# Synchronous_Buck_Solar_Charge_Controller.net
KiCad netlist of a schematic drawn in Altium Designer
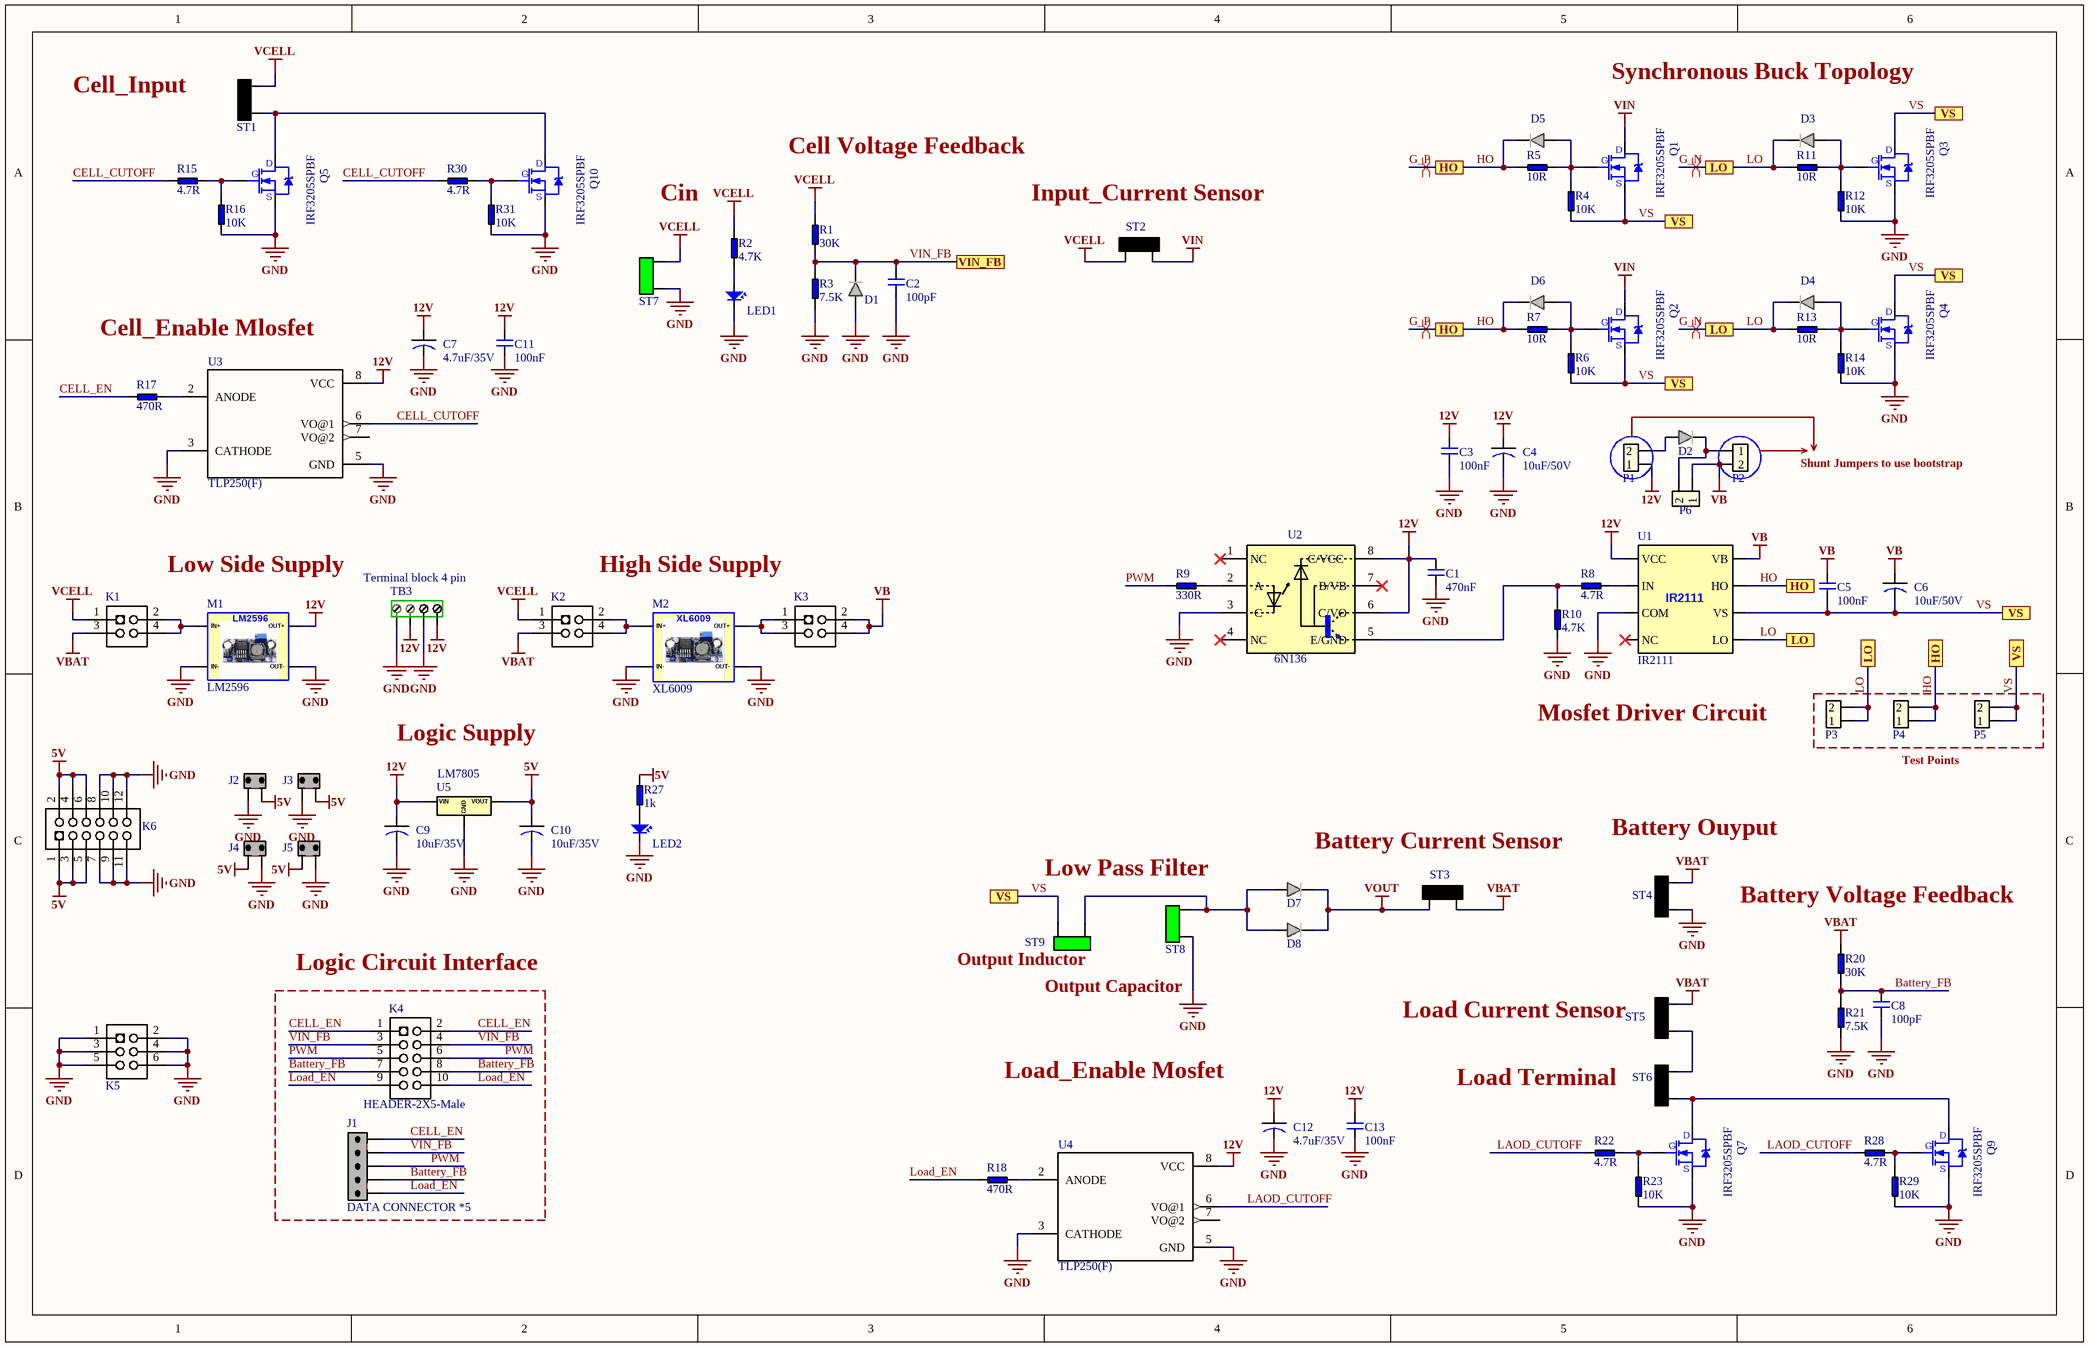
[diagram p0: Synchronous Buck Solar Charge Controller Board.SchDoc]

(export (version "E")
  (design (tool "Eeschema 10.0.6"))
  (components
    (comp (ref "C1")
      (value "470nF")
      (footprint "CCAP 0.1 N Y")
      (libsource (lib "Altium_Abbas") (part "Ceramic_CAP_470nF"))
    )
    (comp (ref "C2")
      (value "100pF")
      (footprint "CCAP 0.1 N Y")
      (libsource (lib "Altium_Abbas") (part "Ceramic_CAP_100pF"))
    )
    (comp (ref "C3")
      (value "100nF")
      (footprint "CCAP 0.1 N Y")
      (libsource (lib "Altium_Abbas") (part "Ceramic_CAP_100nF"))
    )
    (comp (ref "C4")
      (value "10uF/50V")
      (footprint "ECAP 5X11X2MM")
      (description "10uF ±20% 50V 5x11 1000Hrs @ 105℃ Radial,5x11mm Aluminum Electrolytic Capacitors - Leaded RoHS")
      (libsource (lib "Altium_Abbas") (part "ECAP-10uF-50V"))
    )
    (comp (ref "C5")
      (value "100nF")
      (footprint "CCAP 0.1 N Y")
      (libsource (lib "Altium_Abbas") (part "Ceramic_CAP_100nF"))
    )
    (comp (ref "C6")
      (value "10uF/50V")
      (footprint "ECAP 5X11X2MM")
      (description "10uF ±20% 50V 5x11 1000Hrs @ 105℃ Radial,5x11mm Aluminum Electrolytic Capacitors - Leaded RoHS")
      (libsource (lib "Altium_Abbas") (part "ECAP-10uF-50V"))
    )
    (comp (ref "C7")
      (value "4.7uF/35V")
      (footprint "ECAP 5X11X2MM")
      (description "4.7uF ±20% 35V 5x11 7000Hrs @ 105℃ Radial,5x11mm Aluminum Electrolytic Capacitors - Leaded RoHS")
      (libsource (lib "Altium_Abbas") (part "ECAP-4.7uF-35V"))
    )
    (comp (ref "C8")
      (value "100pF")
      (footprint "CCAP 0.1 N Y")
      (libsource (lib "Altium_Abbas") (part "Ceramic_CAP_100pF"))
    )
    (comp (ref "C9")
      (value "10uF/35V")
      (footprint "ECAP 5X11X2MM")
      (description "10uF ±20% 35V 5x11 2000Hrs @ 105℃ Radial,5x11mm Aluminum Electrolytic Capacitors - Leaded RoHS")
      (libsource (lib "Altium_Abbas") (part "ECAP-10uF-35V"))
    )
    (comp (ref "C10")
      (value "10uF/35V")
      (footprint "ECAP 5X11X2MM")
      (description "10uF ±20% 35V 5x11 2000Hrs @ 105℃ Radial,5x11mm Aluminum Electrolytic Capacitors - Leaded RoHS")
      (libsource (lib "Altium_Abbas") (part "ECAP-10uF-35V"))
    )
    (comp (ref "C11")
      (value "100nF")
      (footprint "CCAP 0.1 N Y")
      (libsource (lib "Altium_Abbas") (part "Ceramic_CAP_100nF"))
    )
    (comp (ref "C12")
      (value "4.7uF/35V")
      (footprint "ECAP 5X11X2MM")
      (description "4.7uF ±20% 35V 5x11 7000Hrs @ 105℃ Radial,5x11mm Aluminum Electrolytic Capacitors - Leaded RoHS")
      (libsource (lib "Altium_Abbas") (part "ECAP-4.7uF-35V"))
    )
    (comp (ref "C13")
      (value "100nF")
      (footprint "CCAP 0.1 N Y")
      (libsource (lib "Altium_Abbas") (part "Ceramic_CAP_100nF"))
    )
    (comp (ref "D1")
      (value "DIODE")
      (footprint "DIODE-1N400X_0.1")
      (libsource (lib "Altium_Abbas") (part "DIODE"))
    )
    (comp (ref "D2")
      (value "DIODE")
      (footprint "DIODE-1n400X_0.3")
      (libsource (lib "Altium_Abbas") (part "DIODE"))
    )
    (comp (ref "D3")
      (value "DIODE")
      (footprint "DIODE-1n400X_0.3")
      (libsource (lib "Altium_Abbas") (part "DIODE"))
    )
    (comp (ref "D4")
      (value "DIODE")
      (footprint "DIODE-1n400X_0.3")
      (libsource (lib "Altium_Abbas") (part "DIODE"))
    )
    (comp (ref "D5")
      (value "DIODE")
      (footprint "DIODE-1n400X_0.3")
      (libsource (lib "Altium_Abbas") (part "DIODE"))
    )
    (comp (ref "D6")
      (value "DIODE")
      (footprint "DIODE-1n400X_0.3")
      (libsource (lib "Altium_Abbas") (part "DIODE"))
    )
    (comp (ref "D7")
      (value "10A DIODE")
      (footprint "DIODE 10A 0.75")
      (description "10A05-THRU-10A10\r\nVOLTAGE RANGE 50 to 1000 Volts CURRENT 10 Amperes")
      (libsource (lib "Altium_Abbas") (part "DIODE_10A05"))
    )
    (comp (ref "D8")
      (value "10A DIODE")
      (footprint "DIODE 10A 0.75")
      (description "10A05-THRU-10A10\r\nVOLTAGE RANGE 50 to 1000 Volts CURRENT 10 Amperes")
      (libsource (lib "Altium_Abbas") (part "DIODE_10A05"))
    )
    (comp (ref "J1")
      (value "DATA CONNECTOR *5")
      (footprint "MOLEX *5_DATA CONNECTOR")
      (description "Data Cable JST 5-pin")
      (libsource (lib "Altium_Abbas") (part "DATA CONNECTOR *5"))
    )
    (comp (ref "J2")
      (value "DATA CONNECTOR *2")
      (footprint "MOLEX *2_DATA CONNECTOR")
      (description "Data Cable JST 2-pin")
      (libsource (lib "Altium_Abbas") (part "DATA CONNECTOR *2"))
    )
    (comp (ref "J3")
      (value "DATA CONNECTOR *2")
      (footprint "MOLEX *2_DATA CONNECTOR")
      (description "Data Cable JST 2-pin")
      (libsource (lib "Altium_Abbas") (part "DATA CONNECTOR *2"))
    )
    (comp (ref "J4")
      (value "DATA CONNECTOR *2")
      (footprint "MOLEX *2_DATA CONNECTOR")
      (description "Data Cable JST 2-pin")
      (libsource (lib "Altium_Abbas") (part "DATA CONNECTOR *2"))
    )
    (comp (ref "J5")
      (value "DATA CONNECTOR *2")
      (footprint "MOLEX *2_DATA CONNECTOR")
      (description "Data Cable JST 2-pin")
      (libsource (lib "Altium_Abbas") (part "DATA CONNECTOR *2"))
    )
    (comp (ref "K1")
      (value "HEADER-2X2-Male")
      (footprint "HEADER-2X2")
      (libsource (lib "Altium_Abbas") (part "HEADER-2X2-Male"))
    )
    (comp (ref "K2")
      (value "HEADER-2X2-Male")
      (footprint "HEADER-2X2")
      (libsource (lib "Altium_Abbas") (part "HEADER-2X2-Male"))
    )
    (comp (ref "K3")
      (value "HEADER-2X2-Male")
      (footprint "HEADER-2X2")
      (libsource (lib "Altium_Abbas") (part "HEADER-2X2-Male"))
    )
    (comp (ref "K4")
      (value "HEADER-2X5-Male")
      (footprint "HEADER-2X5")
      (libsource (lib "Altium_Abbas") (part "HEADER-2X5-Male"))
    )
    (comp (ref "K5")
      (value "HEADER-2X3-Male")
      (footprint "HEADER-2X3")
      (libsource (lib "Altium_Abbas") (part "HEADER-2X3-Male"))
    )
    (comp (ref "K6")
      (value "HEADER-2X6-Male")
      (footprint "HEADER-2X6")
      (libsource (lib "Altium_Abbas") (part "HEADER-2X6-Male"))
    )
    (comp (ref "LED1")
      (value "LED")
      (footprint "LED 3MM GREEN")
      (libsource (lib "Altium_Abbas") (part "LED"))
    )
    (comp (ref "LED2") (value "LED") (footprint "LED 3MM BLUE") (libsource (lib "Altium_Abbas") (part "LED")))
    (comp (ref "M1")
      (value "LM2596")
      (footprint "LM2956S BUCK CONVETER")
      (description "ADJUSTABLE DC/DC POWER CONVERTER")
      (libsource (lib "Boards_Abbas") (part "DC TO DC CONVERTER LM2596"))
    )
    (comp (ref "M2")
      (value "XL6009")
      (footprint "DC TO DC CONVERTER XL6009")
      (description "ADJUSTABLE DC/DC POWER CONVERTER")
      (libsource (lib "Boards_Abbas") (part "DC TO DC CONVERTER XL6009"))
    )
    (comp (ref "P1")
      (value "Header - 2 - Male")
      (footprint "PINHEADER X2")
      (description "Header, 2-Pin")
      (fields (field (name "PUBLISHER") "Altium Limited"))
      (libsource (lib "Altium_Abbas") (part "Header - 2 - Male"))
    )
    (comp (ref "P2")
      (value "Header - 2 - Male")
      (footprint "PINHEADER X2")
      (description "Header, 2-Pin")
      (fields (field (name "PUBLISHER") "Altium Limited"))
      (libsource (lib "") (part "Header - 2 - Male_1"))
    )
    (comp (ref "P3")
      (value "Header - 2 - Male")
      (footprint "PINHEADER X2")
      (description "Header, 2-Pin")
      (fields (field (name "PUBLISHER") "Altium Limited"))
      (libsource (lib "Altium_Abbas") (part "Header - 2 - Male"))
    )
    (comp (ref "P4")
      (value "Header - 2 - Male")
      (footprint "PINHEADER X2")
      (description "Header, 2-Pin")
      (fields (field (name "PUBLISHER") "Altium Limited"))
      (libsource (lib "Altium_Abbas") (part "Header - 2 - Male"))
    )
    (comp (ref "P5")
      (value "Header - 2 - Male")
      (footprint "PINHEADER X2")
      (description "Header, 2-Pin")
      (fields (field (name "PUBLISHER") "Altium Limited"))
      (libsource (lib "Altium_Abbas") (part "Header - 2 - Male"))
    )
    (comp (ref "P6")
      (value "Header - 2 - Male")
      (footprint "PINHEADER X2")
      (description "Header, 2-Pin")
      (fields (field (name "PUBLISHER") "Altium Limited"))
      (libsource (lib "") (part "Header - 2 - Male_2"))
    )
    (comp (ref "Q1")
      (value "IRF3205SPBF")
      (footprint "Transistor/Heatsink -TO-220")
      (description "N-Channel 55V 110A _Tc_ 200W _Tc_ Surface Mount D2PAK")
      (fields (field (name "MF") "Infineon Technologies"))
      (libsource (lib "Altium_Abbas") (part "IRF3205SPBF"))
    )
    (comp (ref "Q2")
      (value "IRF3205SPBF")
      (footprint "Transistor/Heatsink -TO-220")
      (description "N-Channel 55V 110A _Tc_ 200W _Tc_ Surface Mount D2PAK")
      (fields (field (name "MF") "Infineon Technologies"))
      (libsource (lib "Altium_Abbas") (part "IRF3205SPBF"))
    )
    (comp (ref "Q3")
      (value "IRF3205SPBF")
      (footprint "Transistor/Heatsink -TO-220")
      (description "N-Channel 55V 110A 200W")
      (fields (field (name "MF") "Infineon Technologies"))
      (libsource (lib "Altium_Abbas") (part "IRF3205SPBF"))
    )
    (comp (ref "Q4")
      (value "IRF3205SPBF")
      (footprint "Transistor/Heatsink -TO-220")
      (description "N-Channel 55V 110A 200W")
      (fields (field (name "MF") "Infineon Technologies"))
      (libsource (lib "Altium_Abbas") (part "IRF3205SPBF"))
    )
    (comp (ref "Q5")
      (value "IRF3205SPBF")
      (footprint "Transistor/Heatsink -TO-220")
      (description "N-Channel 55V 110A 200W")
      (fields (field (name "MF") "Infineon Technologies"))
      (libsource (lib "Altium_Abbas") (part "IRF3205SPBF"))
    )
    (comp (ref "Q7")
      (value "IRF3205SPBF")
      (footprint "Transistor/Heatsink -TO-220")
      (description "N-Channel 55V 110A 200W")
      (fields (field (name "MF") "Infineon Technologies"))
      (libsource (lib "Altium_Abbas") (part "IRF3205SPBF"))
    )
    (comp (ref "Q9")
      (value "IRF3205SPBF")
      (footprint "Transistor/Heatsink -TO-220")
      (description "N-Channel 55V 110A 200W")
      (fields (field (name "MF") "Infineon Technologies"))
      (libsource (lib "Altium_Abbas") (part "IRF3205SPBF"))
    )
    (comp (ref "Q10")
      (value "IRF3205SPBF")
      (footprint "Transistor/Heatsink -TO-220")
      (description "N-Channel 55V 110A 200W")
      (fields (field (name "MF") "Infineon Technologies"))
      (libsource (lib "Altium_Abbas") (part "IRF3205SPBF"))
    )
    (comp (ref "R1")
      (value "30K")
      (footprint "RESISTOR _0")
      (libsource (lib "Altium_Abbas") (part "RESISTOR_30K"))
    )
    (comp (ref "R2")
      (value "4.7K")
      (footprint "RESISTOR _1")
      (libsource (lib "Altium_Abbas") (part "RESISTOR_4.7K"))
    )
    (comp (ref "R3")
      (value "7.5K")
      (footprint "RESISTOR _0")
      (libsource (lib "Altium_Abbas") (part "RESISTOR_7.5K"))
    )
    (comp (ref "R4")
      (value "10K")
      (footprint "RESISTOR _1")
      (libsource (lib "Altium_Abbas") (part "RESISTOR_10K"))
    )
    (comp (ref "R5")
      (value "10R")
      (footprint "RESISTOR _1")
      (libsource (lib "Altium_Abbas") (part "RESISTOR_10R"))
    )
    (comp (ref "R6")
      (value "10K")
      (footprint "RESISTOR _1")
      (libsource (lib "Altium_Abbas") (part "RESISTOR_10K"))
    )
    (comp (ref "R7")
      (value "10R")
      (footprint "RESISTOR _1")
      (libsource (lib "Altium_Abbas") (part "RESISTOR_10R"))
    )
    (comp (ref "R8")
      (value "4.7R")
      (footprint "RESISTOR _0")
      (libsource (lib "Altium_Abbas") (part "RESISTOR_4.7R"))
    )
    (comp (ref "R9")
      (value "330R")
      (footprint "RESISTOR _0")
      (libsource (lib "Altium_Abbas") (part "RESISTOR_330R"))
    )
    (comp (ref "R10")
      (value "4.7K")
      (footprint "RESISTOR _0")
      (libsource (lib "Altium_Abbas") (part "RESISTOR_4.7K"))
    )
    (comp (ref "R11")
      (value "10R")
      (footprint "RESISTOR _1")
      (libsource (lib "Altium_Abbas") (part "RESISTOR_10R"))
    )
    (comp (ref "R12")
      (value "10K")
      (footprint "RESISTOR _1")
      (libsource (lib "Altium_Abbas") (part "RESISTOR_10K"))
    )
    (comp (ref "R13")
      (value "10R")
      (footprint "RESISTOR _1")
      (libsource (lib "Altium_Abbas") (part "RESISTOR_10R"))
    )
    (comp (ref "R14")
      (value "10K")
      (footprint "RESISTOR _1")
      (libsource (lib "Altium_Abbas") (part "RESISTOR_10K"))
    )
    (comp (ref "R15")
      (value "4.7R")
      (footprint "RESISTOR _0")
      (libsource (lib "Altium_Abbas") (part "RESISTOR_4.7R"))
    )
    (comp (ref "R16")
      (value "10K")
      (footprint "RESISTOR _0")
      (libsource (lib "Altium_Abbas") (part "RESISTOR_10K"))
    )
    (comp (ref "R17")
      (value "470R")
      (footprint "RESISTOR _0")
      (libsource (lib "Altium_Abbas") (part "RESISTOR_470R"))
    )
    (comp (ref "R18")
      (value "470R")
      (footprint "RESISTOR _0")
      (libsource (lib "Altium_Abbas") (part "RESISTOR_470R"))
    )
    (comp (ref "R20")
      (value "30K")
      (footprint "RESISTOR _1")
      (libsource (lib "Altium_Abbas") (part "RESISTOR_30K"))
    )
    (comp (ref "R21")
      (value "7.5K")
      (footprint "RESISTOR _1")
      (libsource (lib "Altium_Abbas") (part "RESISTOR_7.5K"))
    )
    (comp (ref "R22")
      (value "4.7R")
      (footprint "RESISTOR _0")
      (libsource (lib "Altium_Abbas") (part "RESISTOR_4.7R"))
    )
    (comp (ref "R23")
      (value "10K")
      (footprint "RESISTOR _0")
      (libsource (lib "Altium_Abbas") (part "RESISTOR_10K"))
    )
    (comp (ref "R27")
      (value "1k")
      (footprint "RESISTOR _0")
      (libsource (lib "Altium_Abbas") (part "RESISTOR_1K"))
    )
    (comp (ref "R28")
      (value "4.7R")
      (footprint "RESISTOR _0")
      (libsource (lib "Altium_Abbas") (part "RESISTOR_4.7R"))
    )
    (comp (ref "R29")
      (value "10K")
      (footprint "RESISTOR _0")
      (libsource (lib "Altium_Abbas") (part "RESISTOR_10K"))
    )
    (comp (ref "R30")
      (value "4.7R")
      (footprint "RESISTOR _0")
      (libsource (lib "Altium_Abbas") (part "RESISTOR_4.7R"))
    )
    (comp (ref "R31")
      (value "10K")
      (footprint "RESISTOR _0")
      (libsource (lib "Altium_Abbas") (part "RESISTOR_10K"))
    )
    (comp (ref "ST1")
      (value "SCREW TERMINAL")
      (footprint "SCREW TERMINAL")
      (description "Barrier Terminal Block 2 Pin with cover 300V/25A")
      (libsource (lib "Altium_Abbas") (part "SCREW TERMINAL"))
    )
    (comp (ref "ST2")
      (value "SCREW TERMINAL")
      (footprint "SCREW TERMINAL")
      (description "Barrier Terminal Block 2 Pin with cover 300V/25A")
      (libsource (lib "") (part "SCREW TERMINAL_2"))
    )
    (comp (ref "ST3")
      (value "SCREW TERMINAL")
      (footprint "SCREW TERMINAL")
      (description "Barrier Terminal Block 2 Pin with cover 300V/25A")
      (libsource (lib "") (part "SCREW TERMINAL_2"))
    )
    (comp (ref "ST4")
      (value "SCREW TERMINAL")
      (footprint "SCREW TERMINAL")
      (description "Barrier Terminal Block 2 Pin with cover 300V/25A")
      (libsource (lib "") (part "SCREW TERMINAL_1"))
    )
    (comp (ref "ST5")
      (value "SCREW TERMINAL")
      (footprint "SCREW TERMINAL")
      (description "Barrier Terminal Block 2 Pin with cover 300V/25A")
      (libsource (lib "") (part "SCREW TERMINAL_1"))
    )
    (comp (ref "ST6")
      (value "SCREW TERMINAL")
      (footprint "SCREW TERMINAL")
      (description "Barrier Terminal Block 2 Pin with cover 300V/25A")
      (libsource (lib "") (part "SCREW TERMINAL_1"))
    )
    (comp (ref "ST7")
      (value "2 Pole Power Terminal")
      (footprint "Screw Terminal Green")
      (description "KF762 Power Terminal Pitch 7.62mm Screw Block Connector 300V 20A 3Pin")
      (libsource (lib "Altium_Abbas") (part "Screw Terminal Green"))
    )
    (comp (ref "ST8")
      (value "2 Pole Power Terminal")
      (footprint "Screw Terminal Green")
      (description "KF762 Power Terminal Pitch 7.62mm Screw Block Connector 300V 20A 3Pin")
      (libsource (lib "Altium_Abbas") (part "Screw Terminal Green"))
    )
    (comp (ref "ST9")
      (value "2 Pole Power Terminal")
      (footprint "Screw Terminal Green")
      (description "KF762 Power Terminal Pitch 7.62mm Screw Block Connector 300V 20A 3Pin")
      (libsource (lib "") (part "Screw Terminal Green_1"))
    )
    (comp (ref "TB3")
      (value "Terminal block 4 pin")
      (footprint "AK500/4_BLUE")
      (description "Terminal Block 3 Pin 10A 300V")
      (libsource (lib "Altium_Abbas") (part "Terminal block 4 pin"))
    )
    (comp (ref "U1")
      (value "IR2111")
      (footprint "IC_DIP8")
      (description "IR2111 - 600 V 200/420 mA 20 V Supply Quad High And Low Side Driver - PDIP-8")
      (libsource (lib "Altium_Abbas") (part "IR2111"))
    )
    (comp (ref "U2")
      (value "6N136")
      (footprint "IC_DIP8")
      (description "Optoisolator Transistor with Base Output 5300Vrms 1 Channel 8-DIP")
      (fields (field (name "MF") "Vishay Semiconductor"))
      (libsource (lib "Altium_Abbas") (part "6N136"))
    )
    (comp (ref "U3")
      (value "TLP250(F)")
      (footprint "IC_DIP8")
      (description "Optocoupler; THT; Out: IGBT driver; 2.5kV; DIP8; 1.5A")
      (fields (field (name "MF") "Toshiba") (field (name "MP") "TLP250_F_"))
      (libsource (lib "Altium_Abbas") (part "TLP250(F)"))
    )
    (comp (ref "U4")
      (value "TLP250(F)")
      (footprint "IC_DIP8")
      (description "Optocoupler; THT; Out: IGBT driver; 2.5kV; DIP8; 1.5A")
      (fields (field (name "MF") "Toshiba") (field (name "MP") "TLP250_F_"))
      (libsource (lib "Altium_Abbas") (part "TLP250(F)"))
    )
    (comp (ref "U5")
      (value "LM7805")
      (footprint "V-REG/Heatsink - TO - 220")
      (description "78xx Regulators")
      (libsource (lib "Altium_Abbas") (part "LM7805"))
    )
  )
  (nets
    (net (code "1") (name "/Battery_FB") (class "Default")
      (node (ref "C8") (pin "1") (pintype "passive"))
      (node (ref "J1") (pin "4") (pinfunction "4_4") (pintype "passive"))
      (node (ref "K4") (pin "7") (pintype "passive"))
      (node (ref "K4") (pin "8") (pintype "passive"))
      (node (ref "R20") (pin "1") (pinfunction "5_1") (pintype "passive"))
      (node (ref "R21") (pin "2") (pinfunction "6_2") (pintype "passive"))
    )
    (net (code "2") (name "/CELL_CUTOFF") (class "Default")
      (node (ref "R15") (pin "1") (pinfunction "5_1") (pintype "passive"))
      (node (ref "R30") (pin "1") (pinfunction "5_1") (pintype "passive"))
      (node (ref "U3") (pin "6") (pinfunction "VO@1_6") (pintype "output"))
    )
    (net (code "3") (name "/CELL_EN") (class "Default")
      (node (ref "J1") (pin "1") (pinfunction "1_1") (pintype "passive"))
      (node (ref "K4") (pin "1") (pintype "passive"))
      (node (ref "K4") (pin "2") (pintype "passive"))
      (node (ref "R17") (pin "1") (pinfunction "5_1") (pintype "passive"))
    )
    (net (code "4") (name "/G_N") (class "Default")
      (node (ref "D3") (pin "K") (pintype "passive"))
      (node (ref "D4") (pin "K") (pintype "passive"))
      (node (ref "P3") (pin "1") (pinfunction "1_1") (pintype "passive"))
      (node (ref "P3") (pin "2") (pinfunction "2_2") (pintype "passive"))
      (node (ref "R11") (pin "1") (pinfunction "5_1") (pintype "passive"))
      (node (ref "R13") (pin "1") (pinfunction "5_1") (pintype "passive"))
      (node (ref "U1") (pin "4") (pinfunction "LO_4") (pintype "passive"))
    )
    (net (code "5") (name "/G_P") (class "Default")
      (node (ref "D5") (pin "K") (pintype "passive"))
      (node (ref "D6") (pin "K") (pintype "passive"))
      (node (ref "P4") (pin "1") (pinfunction "1_1") (pintype "passive"))
      (node (ref "P4") (pin "2") (pinfunction "2_2") (pintype "passive"))
      (node (ref "R5") (pin "1") (pinfunction "5_1") (pintype "passive"))
      (node (ref "R7") (pin "1") (pinfunction "5_1") (pintype "passive"))
      (node (ref "U1") (pin "7") (pinfunction "HO_7") (pintype "passive"))
    )
    (net (code "6") (name "/LAOD_CUTOFF") (class "Default")
      (node (ref "R22") (pin "1") (pinfunction "5_1") (pintype "passive"))
      (node (ref "R28") (pin "1") (pinfunction "5_1") (pintype "passive"))
      (node (ref "U4") (pin "6") (pinfunction "VO@1_6") (pintype "output"))
    )
    (net (code "7") (name "/Load_EN") (class "Default")
      (node (ref "J1") (pin "5") (pinfunction "5_5") (pintype "passive"))
      (node (ref "K4") (pin "10") (pintype "passive"))
      (node (ref "K4") (pin "9") (pintype "passive"))
      (node (ref "R18") (pin "1") (pinfunction "5_1") (pintype "passive"))
    )
    (net (code "8") (name "/PWM") (class "Default")
      (node (ref "J1") (pin "3") (pinfunction "3_3") (pintype "passive"))
      (node (ref "K4") (pin "5") (pintype "passive"))
      (node (ref "K4") (pin "6") (pintype "passive"))
      (node (ref "R9") (pin "1") (pinfunction "5_1") (pintype "passive"))
    )
    (net (code "9") (name "/VIN_FB") (class "Default")
      (node (ref "C2") (pin "1") (pintype "passive"))
      (node (ref "D1") (pin "K") (pintype "passive"))
      (node (ref "J1") (pin "2") (pinfunction "2_2") (pintype "passive"))
      (node (ref "K4") (pin "3") (pintype "passive"))
      (node (ref "K4") (pin "4") (pintype "passive"))
      (node (ref "R1") (pin "1") (pinfunction "5_1") (pintype "passive"))
      (node (ref "R3") (pin "2") (pinfunction "6_2") (pintype "passive"))
    )
    (net (code "10") (name "/VS") (class "Default")
      (node (ref "C5") (pin "2") (pintype "passive"))
      (node (ref "C6") (pin "K") (pintype "passive"))
      (node (ref "P5") (pin "1") (pinfunction "1_1") (pintype "passive"))
      (node (ref "P5") (pin "2") (pinfunction "2_2") (pintype "passive"))
      (node (ref "Q1") (pin "3") (pinfunction "S_3") (pintype "passive"))
      (node (ref "Q2") (pin "3") (pinfunction "S_3") (pintype "passive"))
      (node (ref "Q3") (pin "2") (pinfunction "D_2") (pintype "passive"))
      (node (ref "Q4") (pin "2") (pinfunction "D_2") (pintype "passive"))
      (node (ref "R4") (pin "2") (pinfunction "6_2") (pintype "passive"))
      (node (ref "R6") (pin "2") (pinfunction "6_2") (pintype "passive"))
      (node (ref "ST9") (pin "2") (pinfunction "2_2") (pintype "passive"))
      (node (ref "U1") (pin "6") (pinfunction "VS_6") (pintype "passive"))
    )
    (net (code "11") (name "5V") (class "Default")
      (node (ref "C10") (pin "A") (pintype "passive"))
      (node (ref "J2") (pin "1") (pinfunction "1_1") (pintype "passive"))
      (node (ref "J3") (pin "1") (pinfunction "1_1") (pintype "passive"))
      (node (ref "J4") (pin "2") (pinfunction "2_2") (pintype "passive"))
      (node (ref "J5") (pin "2") (pinfunction "2_2") (pintype "passive"))
      (node (ref "K6") (pin "1") (pintype "passive"))
      (node (ref "K6") (pin "2") (pintype "passive"))
      (node (ref "K6") (pin "3") (pintype "passive"))
      (node (ref "K6") (pin "4") (pintype "passive"))
      (node (ref "K6") (pin "5") (pintype "passive"))
      (node (ref "K6") (pin "6") (pintype "passive"))
      (node (ref "R27") (pin "2") (pinfunction "6_2") (pintype "passive"))
      (node (ref "U5") (pin "3") (pinfunction "VOUT_3") (pintype "passive"))
    )
    (net (code "12") (name "12V") (class "Default")
      (node (ref "C1") (pin "1") (pintype "passive"))
      (node (ref "C11") (pin "1") (pintype "passive"))
      (node (ref "C12") (pin "A") (pintype "passive"))
      (node (ref "C13") (pin "1") (pintype "passive"))
      (node (ref "C3") (pin "1") (pintype "passive"))
      (node (ref "C4") (pin "A") (pintype "passive"))
      (node (ref "C7") (pin "A") (pintype "passive"))
      (node (ref "C9") (pin "A") (pintype "passive"))
      (node (ref "M1") (pin "OUT+") (pinfunction "OUT+_OUT+") (pintype "passive"))
      (node (ref "P1") (pin "1") (pinfunction "1_1") (pintype "passive"))
      (node (ref "TB3") (pin "1") (pinfunction "*_1") (pintype "passive"))
      (node (ref "TB3") (pin "3") (pinfunction "*_3") (pintype "passive"))
      (node (ref "U1") (pin "1") (pinfunction "VCC_1") (pintype "passive"))
      (node (ref "U2") (pin "6") (pinfunction "C/VO_6") (pintype "passive"))
      (node (ref "U2") (pin "8") (pinfunction "C/VCC_8") (pintype "passive"))
      (node (ref "U3") (pin "8") (pinfunction "VCC_8") (pintype "power_in"))
      (node (ref "U4") (pin "8") (pinfunction "VCC_8") (pintype "power_in"))
      (node (ref "U5") (pin "1") (pinfunction "VIN_1") (pintype "passive"))
    )
    (net (code "13") (name "GND") (class "Default")
      (node (ref "C1") (pin "2") (pintype "passive"))
      (node (ref "C10") (pin "K") (pintype "passive"))
      (node (ref "C11") (pin "2") (pintype "passive"))
      (node (ref "C12") (pin "K") (pintype "passive"))
      (node (ref "C13") (pin "2") (pintype "passive"))
      (node (ref "C2") (pin "2") (pintype "passive"))
      (node (ref "C3") (pin "2") (pintype "passive"))
      (node (ref "C4") (pin "K") (pintype "passive"))
      (node (ref "C7") (pin "K") (pintype "passive"))
      (node (ref "C8") (pin "2") (pintype "passive"))
      (node (ref "C9") (pin "K") (pintype "passive"))
      (node (ref "D1") (pin "A") (pintype "passive"))
      (node (ref "J2") (pin "2") (pinfunction "2_2") (pintype "passive"))
      (node (ref "J3") (pin "2") (pinfunction "2_2") (pintype "passive"))
      (node (ref "J4") (pin "1") (pinfunction "1_1") (pintype "passive"))
      (node (ref "J5") (pin "1") (pinfunction "1_1") (pintype "passive"))
      (node (ref "K5") (pin "1") (pintype "passive"))
      (node (ref "K5") (pin "2") (pintype "passive"))
      (node (ref "K5") (pin "3") (pintype "passive"))
      (node (ref "K5") (pin "4") (pintype "passive"))
      (node (ref "K5") (pin "5") (pintype "passive"))
      (node (ref "K5") (pin "6") (pintype "passive"))
      (node (ref "K6") (pin "10") (pintype "passive"))
      (node (ref "K6") (pin "11") (pintype "passive"))
      (node (ref "K6") (pin "12") (pintype "passive"))
      (node (ref "K6") (pin "7") (pintype "passive"))
      (node (ref "K6") (pin "8") (pintype "passive"))
      (node (ref "K6") (pin "9") (pintype "passive"))
      (node (ref "LED1") (pin "K") (pintype "passive"))
      (node (ref "LED2") (pin "K") (pintype "passive"))
      (node (ref "M1") (pin "IN-") (pinfunction "IN-_IN-") (pintype "passive"))
      (node (ref "M1") (pin "OUT-") (pinfunction "OUT-_OUT-") (pintype "passive"))
      (node (ref "M2") (pin "IN-") (pinfunction "IN-_IN-") (pintype "passive"))
      (node (ref "M2") (pin "OUT-") (pinfunction "OUT-_OUT-") (pintype "passive"))
      (node (ref "Q10") (pin "3") (pinfunction "S_3") (pintype "passive"))
      (node (ref "Q3") (pin "3") (pinfunction "S_3") (pintype "passive"))
      (node (ref "Q4") (pin "3") (pinfunction "S_3") (pintype "passive"))
      (node (ref "Q5") (pin "3") (pinfunction "S_3") (pintype "passive"))
      (node (ref "Q7") (pin "3") (pinfunction "S_3") (pintype "passive"))
      (node (ref "Q9") (pin "3") (pinfunction "S_3") (pintype "passive"))
      (node (ref "R10") (pin "1") (pinfunction "5_1") (pintype "passive"))
      (node (ref "R12") (pin "1") (pinfunction "5_1") (pintype "passive"))
      (node (ref "R14") (pin "1") (pinfunction "5_1") (pintype "passive"))
      (node (ref "R16") (pin "1") (pinfunction "5_1") (pintype "passive"))
      (node (ref "R21") (pin "1") (pinfunction "5_1") (pintype "passive"))
      (node (ref "R23") (pin "1") (pinfunction "5_1") (pintype "passive"))
      (node (ref "R29") (pin "1") (pinfunction "5_1") (pintype "passive"))
      (node (ref "R3") (pin "1") (pinfunction "5_1") (pintype "passive"))
      (node (ref "R31") (pin "1") (pinfunction "5_1") (pintype "passive"))
      (node (ref "ST4") (pin "1") (pinfunction "AC_1") (pintype "passive"))
      (node (ref "ST7") (pin "1") (pinfunction "1_1") (pintype "passive"))
      (node (ref "ST8") (pin "1") (pinfunction "1_1") (pintype "passive"))
      (node (ref "TB3") (pin "2") (pinfunction "*_2") (pintype "passive"))
      (node (ref "TB3") (pin "4") (pinfunction "*_4") (pintype "passive"))
      (node (ref "U1") (pin "3") (pinfunction "COM_3") (pintype "passive"))
      (node (ref "U2") (pin "3") (pinfunction "C_3") (pintype "passive"))
      (node (ref "U3") (pin "3") (pinfunction "CATHODE_3") (pintype "passive"))
      (node (ref "U3") (pin "5") (pinfunction "GND_5") (pintype "power_in"))
      (node (ref "U4") (pin "3") (pinfunction "CATHODE_3") (pintype "passive"))
      (node (ref "U4") (pin "5") (pinfunction "GND_5") (pintype "power_in"))
      (node (ref "U5") (pin "2") (pinfunction "GND_2") (pintype "passive"))
    )
    (net (code "14") (name "Net-(D2-PadA)") (class "Default")
      (node (ref "D2") (pin "A") (pintype "passive"))
      (node (ref "P1") (pin "2") (pinfunction "2_2") (pintype "passive"))
    )
    (net (code "15") (name "Net-(D2-PadK)") (class "Default")
      (node (ref "D2") (pin "K") (pintype "passive"))
      (node (ref "P2") (pin "1") (pinfunction "1_1") (pintype "passive"))
      (node (ref "P6") (pin "2") (pinfunction "2_2") (pintype "passive"))
    )
    (net (code "16") (name "Net-(D7-PadA)") (class "Default")
      (node (ref "D7") (pin "A") (pintype "passive"))
      (node (ref "D8") (pin "A") (pintype "passive"))
      (node (ref "ST8") (pin "2") (pinfunction "2_2") (pintype "passive"))
      (node (ref "ST9") (pin "1") (pinfunction "1_1") (pintype "passive"))
    )
    (net (code "17") (name "Net-(K1-Pad2)") (class "Default")
      (node (ref "K1") (pin "2") (pintype "passive"))
      (node (ref "K1") (pin "4") (pintype "passive"))
      (node (ref "M1") (pin "IN+") (pinfunction "IN+_IN+") (pintype "passive"))
    )
    (net (code "18") (name "Net-(K2-Pad2)") (class "Default")
      (node (ref "K2") (pin "2") (pintype "passive"))
      (node (ref "K2") (pin "4") (pintype "passive"))
      (node (ref "M2") (pin "IN+") (pinfunction "IN+_IN+") (pintype "passive"))
    )
    (net (code "19") (name "Net-(K3-Pad1)") (class "Default")
      (node (ref "K3") (pin "1") (pintype "passive"))
      (node (ref "K3") (pin "3") (pintype "passive"))
      (node (ref "M2") (pin "OUT+") (pinfunction "OUT+_OUT+") (pintype "passive"))
    )
    (net (code "20") (name "Net-(Q1-G)") (class "Default")
      (node (ref "D5") (pin "A") (pintype "passive"))
      (node (ref "Q1") (pin "1") (pinfunction "G_1") (pintype "passive"))
      (node (ref "R4") (pin "1") (pinfunction "5_1") (pintype "passive"))
      (node (ref "R5") (pin "2") (pinfunction "6_2") (pintype "passive"))
    )
    (net (code "21") (name "Net-(Q2-G)") (class "Default")
      (node (ref "D6") (pin "A") (pintype "passive"))
      (node (ref "Q2") (pin "1") (pinfunction "G_1") (pintype "passive"))
      (node (ref "R6") (pin "1") (pinfunction "5_1") (pintype "passive"))
      (node (ref "R7") (pin "2") (pinfunction "6_2") (pintype "passive"))
    )
    (net (code "22") (name "Net-(Q3-G)") (class "Default")
      (node (ref "D3") (pin "A") (pintype "passive"))
      (node (ref "Q3") (pin "1") (pinfunction "G_1") (pintype "passive"))
      (node (ref "R11") (pin "2") (pinfunction "6_2") (pintype "passive"))
      (node (ref "R12") (pin "2") (pinfunction "6_2") (pintype "passive"))
    )
    (net (code "23") (name "Net-(Q4-G)") (class "Default")
      (node (ref "D4") (pin "A") (pintype "passive"))
      (node (ref "Q4") (pin "1") (pinfunction "G_1") (pintype "passive"))
      (node (ref "R13") (pin "2") (pinfunction "6_2") (pintype "passive"))
      (node (ref "R14") (pin "2") (pinfunction "6_2") (pintype "passive"))
    )
    (net (code "24") (name "Net-(Q5-G)") (class "Default")
      (node (ref "Q5") (pin "1") (pinfunction "G_1") (pintype "passive"))
      (node (ref "R15") (pin "2") (pinfunction "6_2") (pintype "passive"))
      (node (ref "R16") (pin "2") (pinfunction "6_2") (pintype "passive"))
    )
    (net (code "25") (name "Net-(Q7-D)") (class "Default")
      (node (ref "Q7") (pin "2") (pinfunction "D_2") (pintype "passive"))
      (node (ref "Q9") (pin "2") (pinfunction "D_2") (pintype "passive"))
      (node (ref "ST6") (pin "1") (pinfunction "AC_1") (pintype "passive"))
    )
    (net (code "26") (name "Net-(Q7-G)") (class "Default")
      (node (ref "Q7") (pin "1") (pinfunction "G_1") (pintype "passive"))
      (node (ref "R22") (pin "2") (pinfunction "6_2") (pintype "passive"))
      (node (ref "R23") (pin "2") (pinfunction "6_2") (pintype "passive"))
    )
    (net (code "27") (name "Net-(Q9-G)") (class "Default")
      (node (ref "Q9") (pin "1") (pinfunction "G_1") (pintype "passive"))
      (node (ref "R28") (pin "2") (pinfunction "6_2") (pintype "passive"))
      (node (ref "R29") (pin "2") (pinfunction "6_2") (pintype "passive"))
    )
    (net (code "28") (name "Net-(Q10-D)") (class "Default")
      (node (ref "Q10") (pin "2") (pinfunction "D_2") (pintype "passive"))
      (node (ref "Q5") (pin "2") (pinfunction "D_2") (pintype "passive"))
      (node (ref "ST1") (pin "2") (pinfunction "AC_2") (pintype "passive"))
    )
    (net (code "29") (name "Net-(Q10-G)") (class "Default")
      (node (ref "Q10") (pin "1") (pinfunction "G_1") (pintype "passive"))
      (node (ref "R30") (pin "2") (pinfunction "6_2") (pintype "passive"))
      (node (ref "R31") (pin "2") (pinfunction "6_2") (pintype "passive"))
    )
    (net (code "30") (name "Net-(R2-5)") (class "Default")
      (node (ref "LED1") (pin "A") (pintype "passive"))
      (node (ref "R2") (pin "1") (pinfunction "5_1") (pintype "passive"))
    )
    (net (code "31") (name "Net-(R8-6)") (class "Default")
      (node (ref "R8") (pin "2") (pinfunction "6_2") (pintype "passive"))
      (node (ref "U1") (pin "2") (pinfunction "IN_2") (pintype "passive"))
    )
    (net (code "32") (name "Net-(R9-6)") (class "Default")
      (node (ref "R9") (pin "2") (pinfunction "6_2") (pintype "passive"))
      (node (ref "U2") (pin "2") (pinfunction "A_2") (pintype "passive"))
    )
    (net (code "33") (name "Net-(R10-6)") (class "Default")
      (node (ref "R10") (pin "2") (pinfunction "6_2") (pintype "passive"))
      (node (ref "R8") (pin "1") (pinfunction "5_1") (pintype "passive"))
      (node (ref "U2") (pin "5") (pinfunction "E/GND_5") (pintype "passive"))
    )
    (net (code "34") (name "Net-(R17-6)") (class "Default")
      (node (ref "R17") (pin "2") (pinfunction "6_2") (pintype "passive"))
      (node (ref "U3") (pin "2") (pinfunction "ANODE_2") (pintype "passive"))
    )
    (net (code "35") (name "Net-(R18-6)") (class "Default")
      (node (ref "R18") (pin "2") (pinfunction "6_2") (pintype "passive"))
      (node (ref "U4") (pin "2") (pinfunction "ANODE_2") (pintype "passive"))
    )
    (net (code "36") (name "Net-(R27-5)") (class "Default")
      (node (ref "LED2") (pin "A") (pintype "passive"))
      (node (ref "R27") (pin "1") (pinfunction "5_1") (pintype "passive"))
    )
    (net (code "37") (name "Net-(ST5-AC-Pad1)") (class "Default")
      (node (ref "ST5") (pin "1") (pinfunction "AC_1") (pintype "passive"))
      (node (ref "ST6") (pin "2") (pinfunction "AC_2") (pintype "passive"))
    )
    (net (code "38") (name "VB") (class "Default")
      (node (ref "C5") (pin "1") (pintype "passive"))
      (node (ref "C6") (pin "A") (pintype "passive"))
      (node (ref "K3") (pin "2") (pintype "passive"))
      (node (ref "K3") (pin "4") (pintype "passive"))
      (node (ref "P2") (pin "2") (pinfunction "2_2") (pintype "passive"))
      (node (ref "P6") (pin "1") (pinfunction "1_1") (pintype "passive"))
      (node (ref "U1") (pin "8") (pinfunction "VB_8") (pintype "passive"))
    )
    (net (code "39") (name "VBAT") (class "Default")
      (node (ref "K1") (pin "3") (pintype "passive"))
      (node (ref "K2") (pin "3") (pintype "passive"))
      (node (ref "R20") (pin "2") (pinfunction "6_2") (pintype "passive"))
      (node (ref "ST3") (pin "1") (pinfunction "AC_1") (pintype "passive"))
      (node (ref "ST4") (pin "2") (pinfunction "AC_2") (pintype "passive"))
      (node (ref "ST5") (pin "2") (pinfunction "AC_2") (pintype "passive"))
    )
    (net (code "40") (name "VCELL") (class "Default")
      (node (ref "K1") (pin "1") (pintype "passive"))
      (node (ref "K2") (pin "1") (pintype "passive"))
      (node (ref "R1") (pin "2") (pinfunction "6_2") (pintype "passive"))
      (node (ref "R2") (pin "2") (pinfunction "6_2") (pintype "passive"))
      (node (ref "ST1") (pin "1") (pinfunction "AC_1") (pintype "passive"))
      (node (ref "ST2") (pin "2") (pinfunction "AC_2") (pintype "passive"))
      (node (ref "ST7") (pin "2") (pinfunction "2_2") (pintype "passive"))
    )
    (net (code "41") (name "VIN") (class "Default")
      (node (ref "Q1") (pin "2") (pinfunction "D_2") (pintype "passive"))
      (node (ref "Q2") (pin "2") (pinfunction "D_2") (pintype "passive"))
      (node (ref "ST2") (pin "1") (pinfunction "AC_1") (pintype "passive"))
    )
    (net (code "42") (name "VOUT") (class "Default")
      (node (ref "D7") (pin "K") (pintype "passive"))
      (node (ref "D8") (pin "K") (pintype "passive"))
      (node (ref "ST3") (pin "2") (pinfunction "AC_2") (pintype "passive"))
    )
    (net (code "43") (name "unconnected-(U1-NC-Pad5)") (class "Default")
      (node (ref "U1") (pin "5") (pinfunction "NC_5") (pintype "passive+no_connect"))
    )
    (net (code "44") (name "unconnected-(U2-B{slash}VB-Pad7)") (class "Default")
      (node (ref "U2") (pin "7") (pinfunction "B/VB_7") (pintype "passive+no_connect"))
    )
    (net (code "45") (name "unconnected-(U2-NC-Pad1)") (class "Default")
      (node (ref "U2") (pin "1") (pinfunction "NC_1") (pintype "passive+no_connect"))
    )
    (net (code "46") (name "unconnected-(U2-NC-Pad4)") (class "Default")
      (node (ref "U2") (pin "4") (pinfunction "NC_4") (pintype "passive+no_connect"))
    )
    (net (code "47") (name "unconnected-(U3-VO@2-Pad7)") (class "Default")
      (node (ref "U3") (pin "7") (pinfunction "VO@2_7") (pintype "output"))
    )
    (net (code "48") (name "unconnected-(U4-VO@2-Pad7)") (class "Default")
      (node (ref "U4") (pin "7") (pinfunction "VO@2_7") (pintype "output"))
    )
  )
)
